# PreAmp.net
KiCad netlist of a schematic drawn in Altium Designer
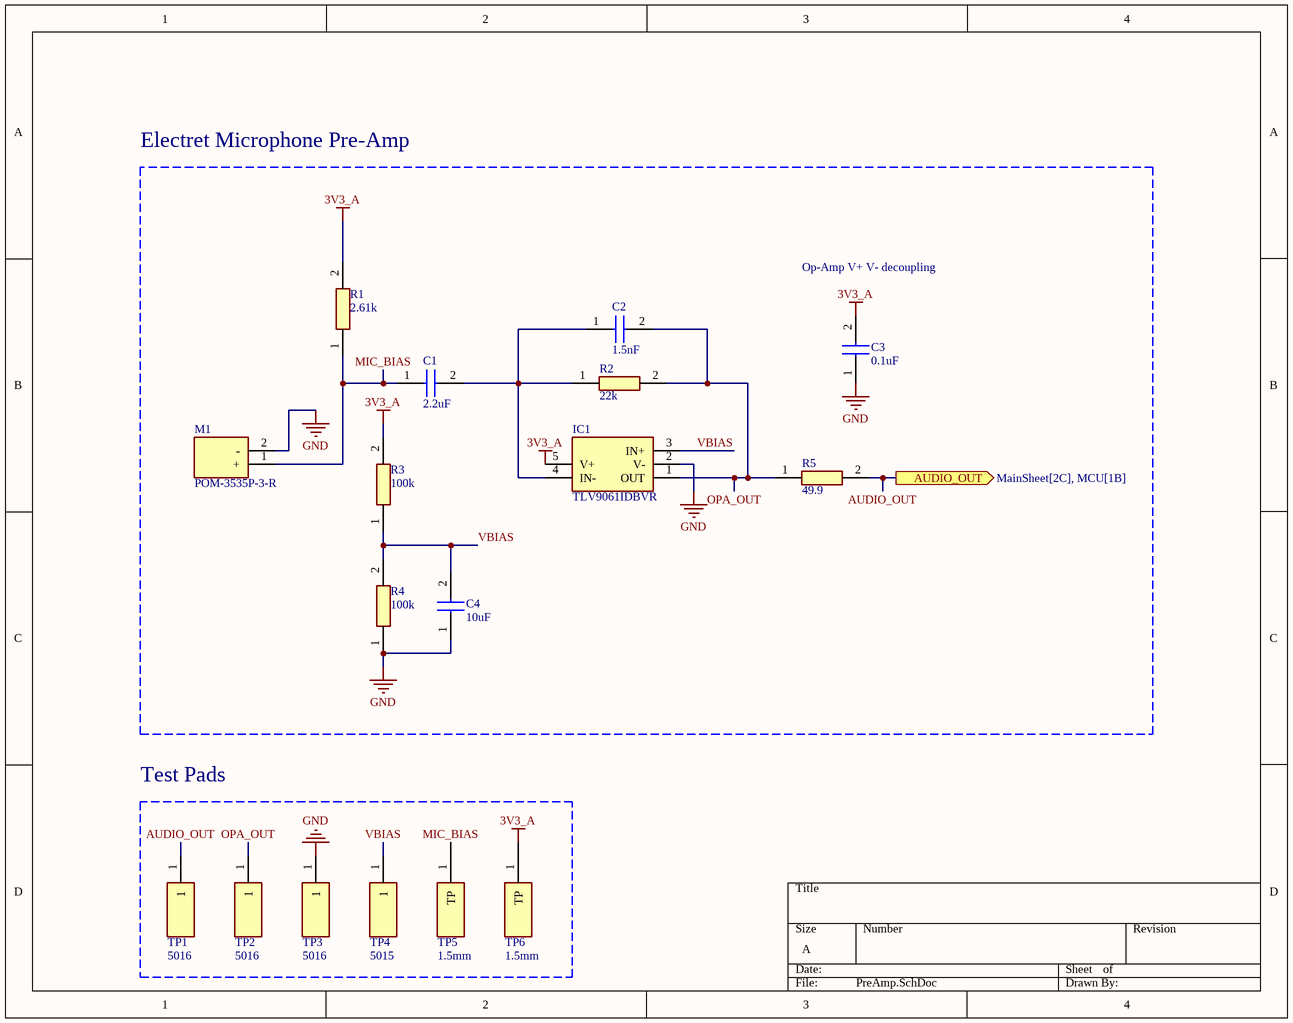
[diagram p0: PreAmp.SchDoc]

(export (version "E")
  (design (tool "Eeschema 10.0.6"))
  (components
    (comp (ref "C1")
      (value "2.2uF")
      (footprint "SamacSys:C0805")
      (description "Capacitor")
      (fields
        (field (name "MANUFACTURER_PART_NUMBER") "C0805C225K8PACTU")
        (field (name "MOUSER PART NUMBER") "80-C0805C225K8P")
      )
      (libsource (lib "Schlib1") (part "2.2uF Capacitor 0805"))
    )
    (comp (ref "C2")
      (value "1.5nF")
      (footprint "PcbLib1:C0805")
      (description "Capacitor")
      (fields (field (name "MANUFACTURER_PART_NUMBER") "C0805C152J5GACTU"))
      (libsource (lib "Schlib1") (part "1.5nF Capaciator 0805"))
    )
    (comp (ref "C3")
      (value "0.1uF")
      (footprint "SamacSys:CAPC2012X88N")
      (description "Capacitor")
      (fields (field (name "MANUFACTURER_PART_NUMBER") "C0805C104K5RAC-TU"))
      (libsource (lib "Schlib1") (part "0.1uF Capacitor 0805"))
    )
    (comp (ref "C4")
      (value "10uF")
      (footprint "SamacSys:CAPC2012X140N")
      (description "Capacitor")
      (fields (field (name "MANUFACTURER_PART_NUMBER") "C0805C106K8PACTU-2.5"))
      (libsource (lib "Schlib1") (part "10uF Capacitor 0805"))
    )
    (comp (ref "IC1")
      (value "TLV9061IDBVR")
      (footprint "SamacSys:SOT95P280X145-5N")
      (description "Integrated Circuit")
      (fields (field (name "MOUSER PART NUMBER") "595-TLV9061IDBVR"))
      (libsource (lib "Schlib1") (part "TLV9061IDBVR"))
    )
    (comp (ref "M1")
      (value "POM-3535P-3-R")
      (footprint "SamacSys:POM3535P3R")
      (description "Microphone")
      (fields (field (name "MOUSER PART NUMBER") "665-POM-3535P-3-R"))
      (libsource (lib "Schlib1") (part "Electret Microphone"))
    )
    (comp (ref "R1")
      (value "2.61k")
      (footprint "SamacSys:RESC2012X60N")
      (description "Resistor")
      (fields
        (field (name "MANUFACTURER_PART_NUMBER") "RC0805FR-072K61L")
        (field (name "MOUSER PART NUMBER") "603-RC0805FR-072K61L")
      )
      (libsource (lib "Schlib1") (part "2.61k Resistor 0805"))
    )
    (comp (ref "R2")
      (value "22k")
      (footprint "PcbLib1:RESC2012X50N")
      (description "Resistor")
      (fields
        (field (name "MANUFACTURER_PART_NUMBER") "CRCW080522K0FKEA")
        (field (name "MOUSER PART NUMBER") "71-CRCW0805-22K-E3")
      )
      (libsource (lib "Schlib1") (part "22k Resistor 0805"))
    )
    (comp (ref "R3")
      (value "100k")
      (footprint "SamacSys:RESC2012X60N")
      (description "Resistor")
      (fields
        (field (name "MANUFACTURER_PART_NUMBER") "CRCW0805100KFKEAHP")
        (field (name "MOUSER PART NUMBER") "71-CRCW0805100KFKEAH")
      )
      (libsource (lib "Schlib1") (part "100k Resistor"))
    )
    (comp (ref "R4")
      (value "100k")
      (footprint "SamacSys:RESC2012X60N")
      (description "Resistor")
      (fields
        (field (name "MANUFACTURER_PART_NUMBER") "CRCW0805100KFKEAHP")
        (field (name "MOUSER PART NUMBER") "71-CRCW0805100KFKEAH")
      )
      (libsource (lib "Schlib1") (part "100k Resistor"))
    )
    (comp (ref "R5")
      (value "49.9")
      (footprint "SamacSys:RESC2012X50N")
      (description "Resistor")
      (fields
        (field (name "MANUFACTURER_PART_NUMBER") "CRCW080549R9FKEA")
        (field (name "MOUSER PART NUMBER") "71-CRCW0805-49.9-E3")
      )
      (libsource (lib "Schlib1") (part "49.9 Resistor"))
    )
    (comp (ref "TP1")
      (value "5016")
      (footprint "SamacSys:5016")
      (description "Test Pad")
      (fields (field (name "MOUSER PART NUMBER") "534-5016"))
      (libsource (lib "Schlib1") (part "5016"))
    )
    (comp (ref "TP2")
      (value "5016")
      (footprint "SamacSys:5016")
      (description "Test Pad")
      (fields (field (name "MOUSER PART NUMBER") "534-5016"))
      (libsource (lib "Schlib1") (part "5016"))
    )
    (comp (ref "TP3")
      (value "5016")
      (footprint "SamacSys:5016")
      (description "Test Pad")
      (fields (field (name "MOUSER PART NUMBER") "534-5016"))
      (libsource (lib "Schlib1") (part "5016"))
    )
    (comp (ref "TP4")
      (value "5015")
      (footprint "SamacSys:5015")
      (description "Test Pad")
      (fields (field (name "MOUSER PART NUMBER") "534-5015"))
      (libsource (lib "Schlib1") (part "5015"))
    )
    (comp (ref "TP5")
      (value "1.5mm")
      (footprint "PcbLib1:TESTPAD_1P5MM")
      (description "1.5mm Bare Test Pad")
      (libsource (lib "Schlib1") (part "TEST_POINT_1PIN"))
    )
    (comp (ref "TP6")
      (value "1.5mm")
      (footprint "PcbLib1:TESTPAD_1P5MM")
      (description "1.5mm Bare Test Pad")
      (libsource (lib "Schlib1") (part "TEST_POINT_1PIN"))
    )
  )
  (nets
    (net (code "1") (name "/AUDIO_OUT") (class "Default")
      (node (ref "R5") (pin "2") (pinfunction "2_2") (pintype "passive"))
      (node (ref "TP1") (pin "1") (pinfunction "1_1") (pintype "passive"))
    )
    (net (code "2") (name "/MIC_BIAS") (class "Default")
      (node (ref "C1") (pin "1") (pinfunction "1_1") (pintype "passive"))
      (node (ref "M1") (pin "1") (pinfunction "+_1") (pintype "passive"))
      (node (ref "R1") (pin "1") (pinfunction "1_1") (pintype "passive"))
      (node (ref "TP5") (pin "1") (pinfunction "TP_1") (pintype "passive"))
    )
    (net (code "3") (name "/OPA_OUT") (class "Default")
      (node (ref "C2") (pin "2") (pinfunction "2_2") (pintype "passive"))
      (node (ref "IC1") (pin "1") (pinfunction "OUT_1") (pintype "passive"))
      (node (ref "R2") (pin "2") (pinfunction "2_2") (pintype "passive"))
      (node (ref "R5") (pin "1") (pinfunction "1_1") (pintype "passive"))
      (node (ref "TP2") (pin "1") (pinfunction "1_1") (pintype "passive"))
    )
    (net (code "4") (name "/VBIAS") (class "Default")
      (node (ref "C4") (pin "2") (pinfunction "2_2") (pintype "passive"))
      (node (ref "IC1") (pin "3") (pinfunction "IN+_3") (pintype "passive"))
      (node (ref "R3") (pin "1") (pinfunction "1_1") (pintype "passive"))
      (node (ref "R4") (pin "2") (pinfunction "2_2") (pintype "passive"))
      (node (ref "TP4") (pin "1") (pinfunction "1_1") (pintype "passive"))
    )
    (net (code "5") (name "3V3_A") (class "Default")
      (node (ref "C3") (pin "2") (pinfunction "2_2") (pintype "passive"))
      (node (ref "IC1") (pin "5") (pinfunction "V+_5") (pintype "passive"))
      (node (ref "R1") (pin "2") (pinfunction "2_2") (pintype "passive"))
      (node (ref "R3") (pin "2") (pinfunction "2_2") (pintype "passive"))
      (node (ref "TP6") (pin "1") (pinfunction "TP_1") (pintype "passive"))
    )
    (net (code "6") (name "GND") (class "Default")
      (node (ref "C3") (pin "1") (pinfunction "1_1") (pintype "passive"))
      (node (ref "C4") (pin "1") (pinfunction "1_1") (pintype "passive"))
      (node (ref "IC1") (pin "2") (pinfunction "V-_2") (pintype "passive"))
      (node (ref "M1") (pin "2") (pinfunction "-_2") (pintype "passive"))
      (node (ref "R4") (pin "1") (pinfunction "1_1") (pintype "passive"))
      (node (ref "TP3") (pin "1") (pinfunction "1_1") (pintype "passive"))
    )
    (net (code "7") (name "Net-(IC1-IN-)") (class "Default")
      (node (ref "C1") (pin "2") (pinfunction "2_2") (pintype "passive"))
      (node (ref "C2") (pin "1") (pinfunction "1_1") (pintype "passive"))
      (node (ref "IC1") (pin "4") (pinfunction "IN-_4") (pintype "passive"))
      (node (ref "R2") (pin "1") (pinfunction "1_1") (pintype "passive"))
    )
  )
)
